# SmartToy_FirstPage_Board_REV01.net
KiCad netlist of a schematic drawn in Altium Designer
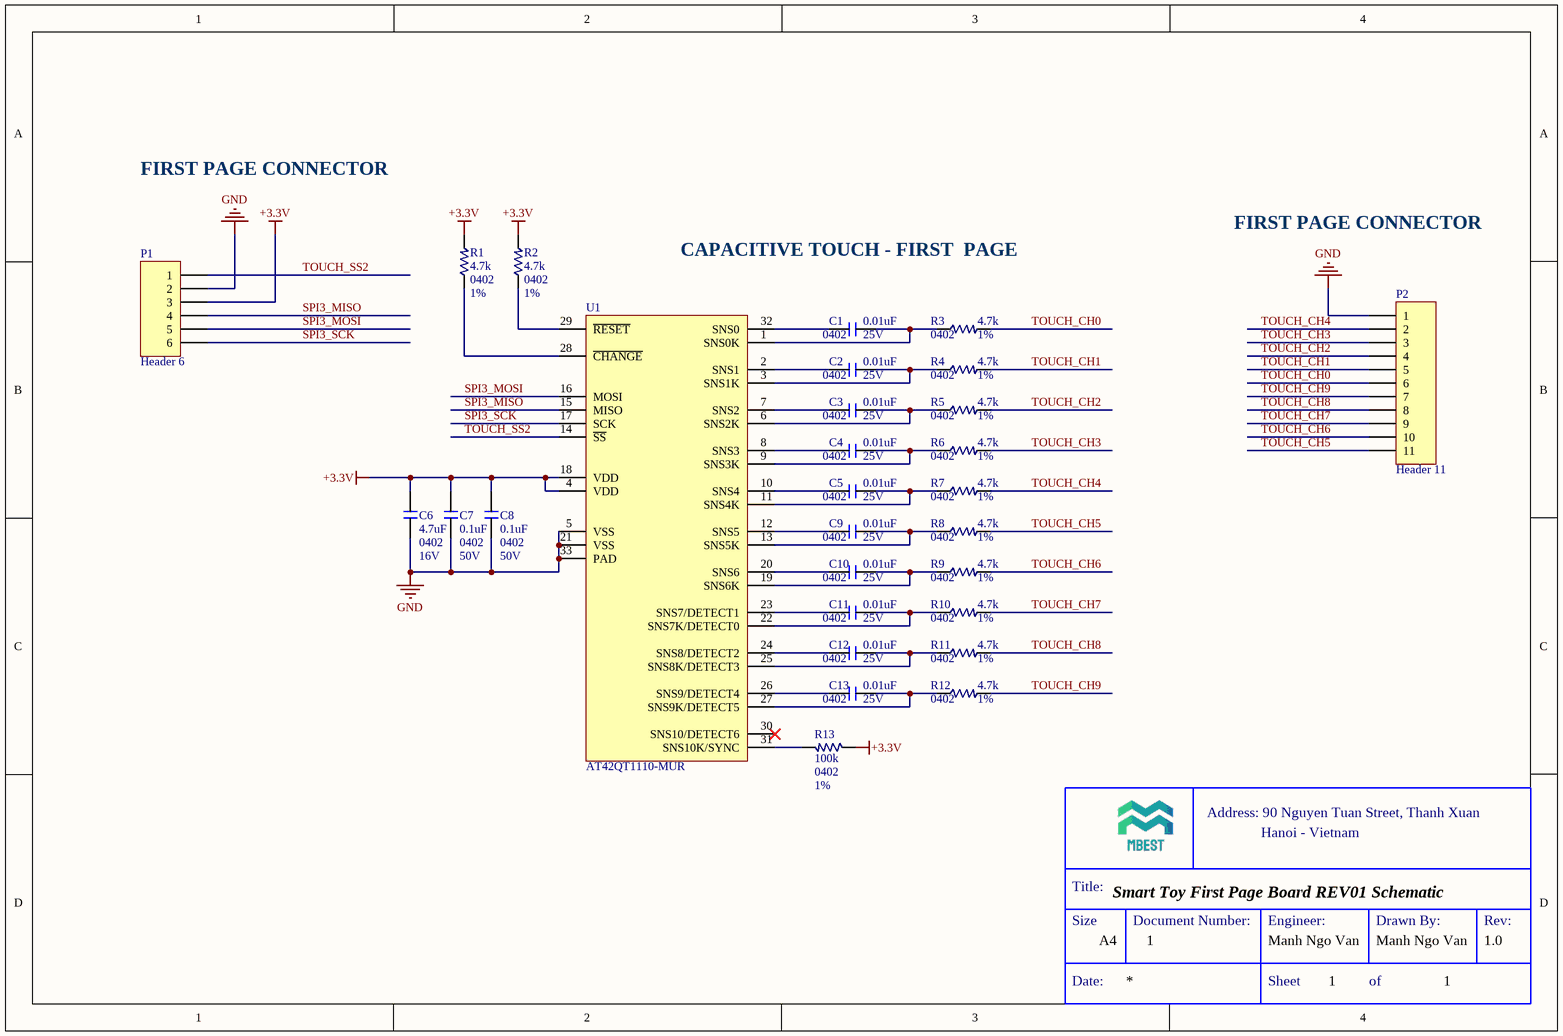
[diagram p0: SmartToy_FirstPage Board_REV01.SchDoc]

(export (version "E")
  (design (tool "Eeschema 10.0.6"))
  (components
    (comp (ref "C1")
      (value "0.01uF")
      (footprint "C0402M")
      (description "CAP CER 10000PF 25V X7R 0402")
      (fields
        (field (name "MANUFACTURER") "Samsung")
        (field (name "MANUFACTURER PART NUMBER") "CL05B103KA5NNNC")
        (field (name "CASE/PACKAGE") "0402")
        (field (name "VOLTAGE RATING") "25V")
      )
      (libsource (lib "CommonLib") (part "CAP_CER"))
    )
    (comp (ref "C2")
      (value "0.01uF")
      (footprint "C0402M")
      (description "CAP CER 10000PF 25V X7R 0402")
      (fields
        (field (name "MANUFACTURER") "Samsung")
        (field (name "MANUFACTURER PART NUMBER") "CL05B103KA5NNNC")
        (field (name "CASE/PACKAGE") "0402")
        (field (name "VOLTAGE RATING") "25V")
      )
      (libsource (lib "CommonLib") (part "CAP_CER"))
    )
    (comp (ref "C3")
      (value "0.01uF")
      (footprint "C0402M")
      (description "CAP CER 10000PF 25V X7R 0402")
      (fields
        (field (name "MANUFACTURER") "Samsung")
        (field (name "MANUFACTURER PART NUMBER") "CL05B103KA5NNNC")
        (field (name "CASE/PACKAGE") "0402")
        (field (name "VOLTAGE RATING") "25V")
      )
      (libsource (lib "CommonLib") (part "CAP_CER"))
    )
    (comp (ref "C4")
      (value "0.01uF")
      (footprint "C0402M")
      (description "CAP CER 10000PF 25V X7R 0402")
      (fields
        (field (name "MANUFACTURER") "Samsung")
        (field (name "MANUFACTURER PART NUMBER") "CL05B103KA5NNNC")
        (field (name "CASE/PACKAGE") "0402")
        (field (name "VOLTAGE RATING") "25V")
      )
      (libsource (lib "CommonLib") (part "CAP_CER"))
    )
    (comp (ref "C5")
      (value "0.01uF")
      (footprint "C0402M")
      (description "CAP CER 10000PF 25V X7R 0402")
      (fields
        (field (name "MANUFACTURER") "Samsung")
        (field (name "MANUFACTURER PART NUMBER") "CL05B103KA5NNNC")
        (field (name "CASE/PACKAGE") "0402")
        (field (name "VOLTAGE RATING") "25V")
      )
      (libsource (lib "CommonLib") (part "CAP_CER"))
    )
    (comp (ref "C6")
      (value "4.7uF")
      (footprint "C0402M")
      (description "CAP CER 4.7UF 16V X5R 0402")
      (fields
        (field (name "MANUFACTURER") "Samsung")
        (field (name "MANUFACTURER PART NUMBER") "CL05A475MO5NUNC")
        (field (name "CASE/PACKAGE") "0402")
        (field (name "VOLTAGE RATING") "16V")
      )
      (libsource (lib "CommonLib") (part "CAP_CER"))
    )
    (comp (ref "C7")
      (value "0.1uF")
      (footprint "C0402M")
      (description "CAP CER 0.1UF 50V X7R 0402")
      (fields
        (field (name "MANUFACTURER") "Murata")
        (field (name "MANUFACTURER PART NUMBER") "GRM155R71H104KE14D")
        (field (name "CASE/PACKAGE") "0402")
        (field (name "VOLTAGE") "50V")
      )
      (libsource (lib "CommonLib") (part "CAP_CER"))
    )
    (comp (ref "C8")
      (value "0.1uF")
      (footprint "C0402M")
      (description "CAP CER 0.1UF 50V X7R 0402")
      (fields
        (field (name "MANUFACTURER") "Murata")
        (field (name "MANUFACTURER PART NUMBER") "GRM155R71H104KE14D")
        (field (name "CASE/PACKAGE") "0402")
        (field (name "VOLTAGE") "50V")
      )
      (libsource (lib "CommonLib") (part "CAP_CER"))
    )
    (comp (ref "C9")
      (value "0.01uF")
      (footprint "C0402M")
      (description "CAP CER 10000PF 25V X7R 0402")
      (fields
        (field (name "MANUFACTURER") "Samsung")
        (field (name "MANUFACTURER PART NUMBER") "CL05B103KA5NNNC")
        (field (name "CASE/PACKAGE") "0402")
        (field (name "VOLTAGE RATING") "25V")
      )
      (libsource (lib "CommonLib") (part "CAP_CER"))
    )
    (comp (ref "C10")
      (value "0.01uF")
      (footprint "C0402M")
      (description "CAP CER 10000PF 25V X7R 0402")
      (fields
        (field (name "MANUFACTURER") "Samsung")
        (field (name "MANUFACTURER PART NUMBER") "CL05B103KA5NNNC")
        (field (name "CASE/PACKAGE") "0402")
        (field (name "VOLTAGE RATING") "25V")
      )
      (libsource (lib "CommonLib") (part "CAP_CER"))
    )
    (comp (ref "C11")
      (value "0.01uF")
      (footprint "C0402M")
      (description "CAP CER 10000PF 25V X7R 0402")
      (fields
        (field (name "MANUFACTURER") "Samsung")
        (field (name "MANUFACTURER PART NUMBER") "CL05B103KA5NNNC")
        (field (name "CASE/PACKAGE") "0402")
        (field (name "VOLTAGE RATING") "25V")
      )
      (libsource (lib "CommonLib") (part "CAP_CER"))
    )
    (comp (ref "C12")
      (value "0.01uF")
      (footprint "C0402M")
      (description "CAP CER 10000PF 25V X7R 0402")
      (fields
        (field (name "MANUFACTURER") "Samsung")
        (field (name "MANUFACTURER PART NUMBER") "CL05B103KA5NNNC")
        (field (name "CASE/PACKAGE") "0402")
        (field (name "VOLTAGE RATING") "25V")
      )
      (libsource (lib "CommonLib") (part "CAP_CER"))
    )
    (comp (ref "C13")
      (value "0.01uF")
      (footprint "C0402M")
      (description "CAP CER 10000PF 25V X7R 0402")
      (fields
        (field (name "MANUFACTURER") "Samsung")
        (field (name "MANUFACTURER PART NUMBER") "CL05B103KA5NNNC")
        (field (name "CASE/PACKAGE") "0402")
        (field (name "VOLTAGE RATING") "25V")
      )
      (libsource (lib "CommonLib") (part "CAP_CER"))
    )
    (comp (ref "P1")
      (value "Header 6")
      (footprint "HDR1X6")
      (description "Header, 6-Pin")
      (fields (field (name "PUBLISHER") "Altium Limited"))
      (libsource (lib "Miscellaneous Connectors") (part "Header 6"))
    )
    (comp (ref "P2")
      (value "Header 11")
      (footprint "TOUCH_CONTACT")
      (description "Header, 11-Pin")
      (fields (field (name "PUBLISHER") "Altium Limited"))
      (libsource (lib "Miscellaneous Connectors") (part "Header 11"))
    )
    (comp (ref "R1")
      (value "4.7k")
      (footprint "R0402M")
      (description "RES SMD 4.7K OHM 1% 1/16W 0402")
      (fields
        (field (name "MANUFACTURER") "Yageo")
        (field (name "MANUFACTURER PART NUMBER") "RC0402FR-074K7L")
        (field (name "CASE CODE (IMPERIAL)") "0402")
        (field (name "TOLERANCE") "1%")
      )
      (libsource (lib "CommonLib") (part "RES_SMD"))
    )
    (comp (ref "R2")
      (value "4.7k")
      (footprint "R0402M")
      (description "RES SMD 4.7K OHM 1% 1/16W 0402")
      (fields
        (field (name "MANUFACTURER") "Yageo")
        (field (name "MANUFACTURER PART NUMBER") "RC0402FR-074K7L")
        (field (name "CASE CODE (IMPERIAL)") "0402")
        (field (name "TOLERANCE") "1%")
      )
      (libsource (lib "CommonLib") (part "RES_SMD"))
    )
    (comp (ref "R3")
      (value "4.7k")
      (footprint "R0402M")
      (description "RES SMD 4.7K OHM 1% 1/16W 0402")
      (fields
        (field (name "MANUFACTURER") "Yageo")
        (field (name "MANUFACTURER PART NUMBER") "RC0402FR-074K7L")
        (field (name "CASE CODE (IMPERIAL)") "0402")
        (field (name "TOLERANCE") "1%")
      )
      (libsource (lib "CommonLib") (part "RES_SMD"))
    )
    (comp (ref "R4")
      (value "4.7k")
      (footprint "R0402M")
      (description "RES SMD 4.7K OHM 1% 1/16W 0402")
      (fields
        (field (name "MANUFACTURER") "Yageo")
        (field (name "MANUFACTURER PART NUMBER") "RC0402FR-074K7L")
        (field (name "CASE CODE (IMPERIAL)") "0402")
        (field (name "TOLERANCE") "1%")
      )
      (libsource (lib "CommonLib") (part "RES_SMD"))
    )
    (comp (ref "R5")
      (value "4.7k")
      (footprint "R0402M")
      (description "RES SMD 4.7K OHM 1% 1/16W 0402")
      (fields
        (field (name "MANUFACTURER") "Yageo")
        (field (name "MANUFACTURER PART NUMBER") "RC0402FR-074K7L")
        (field (name "CASE CODE (IMPERIAL)") "0402")
        (field (name "TOLERANCE") "1%")
      )
      (libsource (lib "CommonLib") (part "RES_SMD"))
    )
    (comp (ref "R6")
      (value "4.7k")
      (footprint "R0402M")
      (description "RES SMD 4.7K OHM 1% 1/16W 0402")
      (fields
        (field (name "MANUFACTURER") "Yageo")
        (field (name "MANUFACTURER PART NUMBER") "RC0402FR-074K7L")
        (field (name "CASE CODE (IMPERIAL)") "0402")
        (field (name "TOLERANCE") "1%")
      )
      (libsource (lib "CommonLib") (part "RES_SMD"))
    )
    (comp (ref "R7")
      (value "4.7k")
      (footprint "R0402M")
      (description "RES SMD 4.7K OHM 1% 1/16W 0402")
      (fields
        (field (name "MANUFACTURER") "Yageo")
        (field (name "MANUFACTURER PART NUMBER") "RC0402FR-074K7L")
        (field (name "CASE CODE (IMPERIAL)") "0402")
        (field (name "TOLERANCE") "1%")
      )
      (libsource (lib "CommonLib") (part "RES_SMD"))
    )
    (comp (ref "R8")
      (value "4.7k")
      (footprint "R0402M")
      (description "RES SMD 4.7K OHM 1% 1/16W 0402")
      (fields
        (field (name "MANUFACTURER") "Yageo")
        (field (name "MANUFACTURER PART NUMBER") "RC0402FR-074K7L")
        (field (name "CASE CODE (IMPERIAL)") "0402")
        (field (name "TOLERANCE") "1%")
      )
      (libsource (lib "CommonLib") (part "RES_SMD"))
    )
    (comp (ref "R9")
      (value "4.7k")
      (footprint "R0402M")
      (description "RES SMD 4.7K OHM 1% 1/16W 0402")
      (fields
        (field (name "MANUFACTURER") "Yageo")
        (field (name "MANUFACTURER PART NUMBER") "RC0402FR-074K7L")
        (field (name "CASE CODE (IMPERIAL)") "0402")
        (field (name "TOLERANCE") "1%")
      )
      (libsource (lib "CommonLib") (part "RES_SMD"))
    )
    (comp (ref "R10")
      (value "4.7k")
      (footprint "R0402M")
      (description "RES SMD 4.7K OHM 1% 1/16W 0402")
      (fields
        (field (name "MANUFACTURER") "Yageo")
        (field (name "MANUFACTURER PART NUMBER") "RC0402FR-074K7L")
        (field (name "CASE CODE (IMPERIAL)") "0402")
        (field (name "TOLERANCE") "1%")
      )
      (libsource (lib "CommonLib") (part "RES_SMD"))
    )
    (comp (ref "R11")
      (value "4.7k")
      (footprint "R0402M")
      (description "RES SMD 4.7K OHM 1% 1/16W 0402")
      (fields
        (field (name "MANUFACTURER") "Yageo")
        (field (name "MANUFACTURER PART NUMBER") "RC0402FR-074K7L")
        (field (name "CASE CODE (IMPERIAL)") "0402")
        (field (name "TOLERANCE") "1%")
      )
      (libsource (lib "CommonLib") (part "RES_SMD"))
    )
    (comp (ref "R12")
      (value "4.7k")
      (footprint "R0402M")
      (description "RES SMD 4.7K OHM 1% 1/16W 0402")
      (fields
        (field (name "MANUFACTURER") "Yageo")
        (field (name "MANUFACTURER PART NUMBER") "RC0402FR-074K7L")
        (field (name "CASE CODE (IMPERIAL)") "0402")
        (field (name "TOLERANCE") "1%")
      )
      (libsource (lib "CommonLib") (part "RES_SMD"))
    )
    (comp (ref "R13")
      (value "100k")
      (footprint "R0402M")
      (description "RES SMD 100K OHM 1% 1/16W 0402")
      (fields
        (field (name "MANUFACTURER") "Yageo")
        (field (name "MANUFACTURER PART NUMBER") "RC0402FR-07100KL")
        (field (name "CASE CODE (IMPERIAL)") "0402")
        (field (name "TOLERANCE") "1%")
      )
      (libsource (lib "BLE1") (part "RES_SMD"))
    )
    (comp (ref "U1")
      (value "AT42QT1110-MUR")
      (footprint "QFN50P500X500X100_HS-33N")
      (description "Capacitive Touch Screen 11 Key 32-Pin VQFN EP T/R")
      (libsource (lib "SmartToy") (part "AT42QT1110-MUR"))
    )
  )
  (nets
    (net (code "1") (name "+3.3V") (class "Default")
      (node (ref "C6") (pin "1") (pinfunction "1_1") (pintype "passive"))
      (node (ref "C7") (pin "1") (pinfunction "1_1") (pintype "passive"))
      (node (ref "C8") (pin "1") (pinfunction "1_1") (pintype "passive"))
      (node (ref "P1") (pin "3") (pinfunction "3_3") (pintype "passive"))
      (node (ref "R1") (pin "1") (pinfunction "1_1") (pintype "passive"))
      (node (ref "R13") (pin "2") (pinfunction "2_2") (pintype "passive"))
      (node (ref "R2") (pin "1") (pinfunction "1_1") (pintype "passive"))
      (node (ref "U1") (pin "18") (pinfunction "VDD_18") (pintype "passive"))
      (node (ref "U1") (pin "4") (pinfunction "VDD_4") (pintype "passive"))
    )
    (net (code "2") (name "/SPI3_MISO") (class "Default")
      (node (ref "P1") (pin "4") (pinfunction "4_4") (pintype "passive"))
      (node (ref "U1") (pin "15") (pinfunction "MISO_15") (pintype "passive"))
    )
    (net (code "3") (name "/SPI3_MOSI") (class "Default")
      (node (ref "P1") (pin "5") (pinfunction "5_5") (pintype "passive"))
      (node (ref "U1") (pin "16") (pinfunction "MOSI_16") (pintype "passive"))
    )
    (net (code "4") (name "/SPI3_SCK") (class "Default")
      (node (ref "P1") (pin "6") (pinfunction "6_6") (pintype "passive"))
      (node (ref "U1") (pin "17") (pinfunction "SCK_17") (pintype "passive"))
    )
    (net (code "5") (name "/TOUCH_CH0") (class "Default")
      (node (ref "P2") (pin "6") (pinfunction "6_6") (pintype "passive"))
      (node (ref "R3") (pin "1") (pinfunction "1_1") (pintype "passive"))
    )
    (net (code "6") (name "/TOUCH_CH1") (class "Default")
      (node (ref "P2") (pin "5") (pinfunction "5_5") (pintype "passive"))
      (node (ref "R4") (pin "1") (pinfunction "1_1") (pintype "passive"))
    )
    (net (code "7") (name "/TOUCH_CH2") (class "Default")
      (node (ref "P2") (pin "4") (pinfunction "4_4") (pintype "passive"))
      (node (ref "R5") (pin "1") (pinfunction "1_1") (pintype "passive"))
    )
    (net (code "8") (name "/TOUCH_CH3") (class "Default")
      (node (ref "P2") (pin "3") (pinfunction "3_3") (pintype "passive"))
      (node (ref "R6") (pin "1") (pinfunction "1_1") (pintype "passive"))
    )
    (net (code "9") (name "/TOUCH_CH4") (class "Default")
      (node (ref "P2") (pin "2") (pinfunction "2_2") (pintype "passive"))
      (node (ref "R7") (pin "1") (pinfunction "1_1") (pintype "passive"))
    )
    (net (code "10") (name "/TOUCH_CH5") (class "Default")
      (node (ref "P2") (pin "11") (pinfunction "11_11") (pintype "passive"))
      (node (ref "R8") (pin "1") (pinfunction "1_1") (pintype "passive"))
    )
    (net (code "11") (name "/TOUCH_CH6") (class "Default")
      (node (ref "P2") (pin "10") (pinfunction "10_10") (pintype "passive"))
      (node (ref "R9") (pin "1") (pinfunction "1_1") (pintype "passive"))
    )
    (net (code "12") (name "/TOUCH_CH7") (class "Default")
      (node (ref "P2") (pin "9") (pinfunction "9_9") (pintype "passive"))
      (node (ref "R10") (pin "1") (pinfunction "1_1") (pintype "passive"))
    )
    (net (code "13") (name "/TOUCH_CH8") (class "Default")
      (node (ref "P2") (pin "8") (pinfunction "8_8") (pintype "passive"))
      (node (ref "R11") (pin "1") (pinfunction "1_1") (pintype "passive"))
    )
    (net (code "14") (name "/TOUCH_CH9") (class "Default")
      (node (ref "P2") (pin "7") (pinfunction "7_7") (pintype "passive"))
      (node (ref "R12") (pin "1") (pinfunction "1_1") (pintype "passive"))
    )
    (net (code "15") (name "/TOUCH_SS2") (class "Default")
      (node (ref "P1") (pin "1") (pinfunction "1_1") (pintype "passive"))
      (node (ref "U1") (pin "14") (pinfunction "~{SS}_14") (pintype "passive"))
    )
    (net (code "16") (name "GND") (class "Default")
      (node (ref "C6") (pin "2") (pinfunction "2_2") (pintype "passive"))
      (node (ref "C7") (pin "2") (pinfunction "2_2") (pintype "passive"))
      (node (ref "C8") (pin "2") (pinfunction "2_2") (pintype "passive"))
      (node (ref "P1") (pin "2") (pinfunction "2_2") (pintype "passive"))
      (node (ref "P2") (pin "1") (pinfunction "1_1") (pintype "passive"))
      (node (ref "U1") (pin "21") (pinfunction "VSS_21") (pintype "passive"))
      (node (ref "U1") (pin "33") (pinfunction "PAD_33") (pintype "passive"))
      (node (ref "U1") (pin "5") (pinfunction "VSS_5") (pintype "passive"))
    )
    (net (code "17") (name "Net-(U1-SNS0)") (class "Default")
      (node (ref "C1") (pin "2") (pinfunction "2_2") (pintype "passive"))
      (node (ref "U1") (pin "32") (pinfunction "SNS0_32") (pintype "passive"))
    )
    (net (code "18") (name "Net-(U1-SNS0K)") (class "Default")
      (node (ref "C1") (pin "1") (pinfunction "1_1") (pintype "passive"))
      (node (ref "R3") (pin "2") (pinfunction "2_2") (pintype "passive"))
      (node (ref "U1") (pin "1") (pinfunction "SNS0K_1") (pintype "passive"))
    )
    (net (code "19") (name "Net-(U1-SNS1)") (class "Default")
      (node (ref "C2") (pin "2") (pinfunction "2_2") (pintype "passive"))
      (node (ref "U1") (pin "2") (pinfunction "SNS1_2") (pintype "passive"))
    )
    (net (code "20") (name "Net-(U1-SNS1K)") (class "Default")
      (node (ref "C2") (pin "1") (pinfunction "1_1") (pintype "passive"))
      (node (ref "R4") (pin "2") (pinfunction "2_2") (pintype "passive"))
      (node (ref "U1") (pin "3") (pinfunction "SNS1K_3") (pintype "passive"))
    )
    (net (code "21") (name "Net-(U1-SNS2)") (class "Default")
      (node (ref "C3") (pin "2") (pinfunction "2_2") (pintype "passive"))
      (node (ref "U1") (pin "7") (pinfunction "SNS2_7") (pintype "passive"))
    )
    (net (code "22") (name "Net-(U1-SNS2K)") (class "Default")
      (node (ref "C3") (pin "1") (pinfunction "1_1") (pintype "passive"))
      (node (ref "R5") (pin "2") (pinfunction "2_2") (pintype "passive"))
      (node (ref "U1") (pin "6") (pinfunction "SNS2K_6") (pintype "passive"))
    )
    (net (code "23") (name "Net-(U1-SNS3)") (class "Default")
      (node (ref "C4") (pin "2") (pinfunction "2_2") (pintype "passive"))
      (node (ref "U1") (pin "8") (pinfunction "SNS3_8") (pintype "passive"))
    )
    (net (code "24") (name "Net-(U1-SNS3K)") (class "Default")
      (node (ref "C4") (pin "1") (pinfunction "1_1") (pintype "passive"))
      (node (ref "R6") (pin "2") (pinfunction "2_2") (pintype "passive"))
      (node (ref "U1") (pin "9") (pinfunction "SNS3K_9") (pintype "passive"))
    )
    (net (code "25") (name "Net-(U1-SNS4)") (class "Default")
      (node (ref "C5") (pin "2") (pinfunction "2_2") (pintype "passive"))
      (node (ref "U1") (pin "10") (pinfunction "SNS4_10") (pintype "passive"))
    )
    (net (code "26") (name "Net-(U1-SNS4K)") (class "Default")
      (node (ref "C5") (pin "1") (pinfunction "1_1") (pintype "passive"))
      (node (ref "R7") (pin "2") (pinfunction "2_2") (pintype "passive"))
      (node (ref "U1") (pin "11") (pinfunction "SNS4K_11") (pintype "passive"))
    )
    (net (code "27") (name "Net-(U1-SNS5)") (class "Default")
      (node (ref "C9") (pin "2") (pinfunction "2_2") (pintype "passive"))
      (node (ref "U1") (pin "12") (pinfunction "SNS5_12") (pintype "passive"))
    )
    (net (code "28") (name "Net-(U1-SNS5K)") (class "Default")
      (node (ref "C9") (pin "1") (pinfunction "1_1") (pintype "passive"))
      (node (ref "R8") (pin "2") (pinfunction "2_2") (pintype "passive"))
      (node (ref "U1") (pin "13") (pinfunction "SNS5K_13") (pintype "passive"))
    )
    (net (code "29") (name "Net-(U1-SNS6)") (class "Default")
      (node (ref "C10") (pin "2") (pinfunction "2_2") (pintype "passive"))
      (node (ref "U1") (pin "20") (pinfunction "SNS6_20") (pintype "passive"))
    )
    (net (code "30") (name "Net-(U1-SNS6K)") (class "Default")
      (node (ref "C10") (pin "1") (pinfunction "1_1") (pintype "passive"))
      (node (ref "R9") (pin "2") (pinfunction "2_2") (pintype "passive"))
      (node (ref "U1") (pin "19") (pinfunction "SNS6K_19") (pintype "passive"))
    )
    (net (code "31") (name "Net-(U1-SNS7K{slash}DETECT0)") (class "Default")
      (node (ref "C11") (pin "1") (pinfunction "1_1") (pintype "passive"))
      (node (ref "R10") (pin "2") (pinfunction "2_2") (pintype "passive"))
      (node (ref "U1") (pin "22") (pinfunction "SNS7K/DETECT0_22") (pintype "passive"))
    )
    (net (code "32") (name "Net-(U1-SNS7{slash}DETECT1)") (class "Default")
      (node (ref "C11") (pin "2") (pinfunction "2_2") (pintype "passive"))
      (node (ref "U1") (pin "23") (pinfunction "SNS7/DETECT1_23") (pintype "passive"))
    )
    (net (code "33") (name "Net-(U1-SNS8K{slash}DETECT3)") (class "Default")
      (node (ref "C12") (pin "1") (pinfunction "1_1") (pintype "passive"))
      (node (ref "R11") (pin "2") (pinfunction "2_2") (pintype "passive"))
      (node (ref "U1") (pin "25") (pinfunction "SNS8K/DETECT3_25") (pintype "passive"))
    )
    (net (code "34") (name "Net-(U1-SNS8{slash}DETECT2)") (class "Default")
      (node (ref "C12") (pin "2") (pinfunction "2_2") (pintype "passive"))
      (node (ref "U1") (pin "24") (pinfunction "SNS8/DETECT2_24") (pintype "passive"))
    )
    (net (code "35") (name "Net-(U1-SNS9K{slash}DETECT5)") (class "Default")
      (node (ref "C13") (pin "1") (pinfunction "1_1") (pintype "passive"))
      (node (ref "R12") (pin "2") (pinfunction "2_2") (pintype "passive"))
      (node (ref "U1") (pin "27") (pinfunction "SNS9K/DETECT5_27") (pintype "passive"))
    )
    (net (code "36") (name "Net-(U1-SNS9{slash}DETECT4)") (class "Default")
      (node (ref "C13") (pin "2") (pinfunction "2_2") (pintype "passive"))
      (node (ref "U1") (pin "26") (pinfunction "SNS9/DETECT4_26") (pintype "passive"))
    )
    (net (code "37") (name "Net-(U1-SNS10K{slash}SYNC)") (class "Default")
      (node (ref "R13") (pin "1") (pinfunction "1_1") (pintype "passive"))
      (node (ref "U1") (pin "31") (pinfunction "SNS10K/SYNC_31") (pintype "passive"))
    )
    (net (code "38") (name "Net-(U1-~{CHANGE})") (class "Default")
      (node (ref "R1") (pin "2") (pinfunction "2_2") (pintype "passive"))
      (node (ref "U1") (pin "28") (pinfunction "~{CHANGE}_28") (pintype "passive"))
    )
    (net (code "39") (name "Net-(U1-~{RESET})") (class "Default")
      (node (ref "R2") (pin "2") (pinfunction "2_2") (pintype "passive"))
      (node (ref "U1") (pin "29") (pinfunction "~{RESET}_29") (pintype "passive"))
    )
    (net (code "40") (name "unconnected-(U1-SNS10{slash}DETECT6-Pad30)") (class "Default")
      (node (ref "U1") (pin "30") (pinfunction "SNS10/DETECT6_30") (pintype "passive+no_connect"))
    )
  )
)
